# Arduino-Mega-2560-Adapter_2.net
KiCad netlist of a schematic drawn in EAGLE
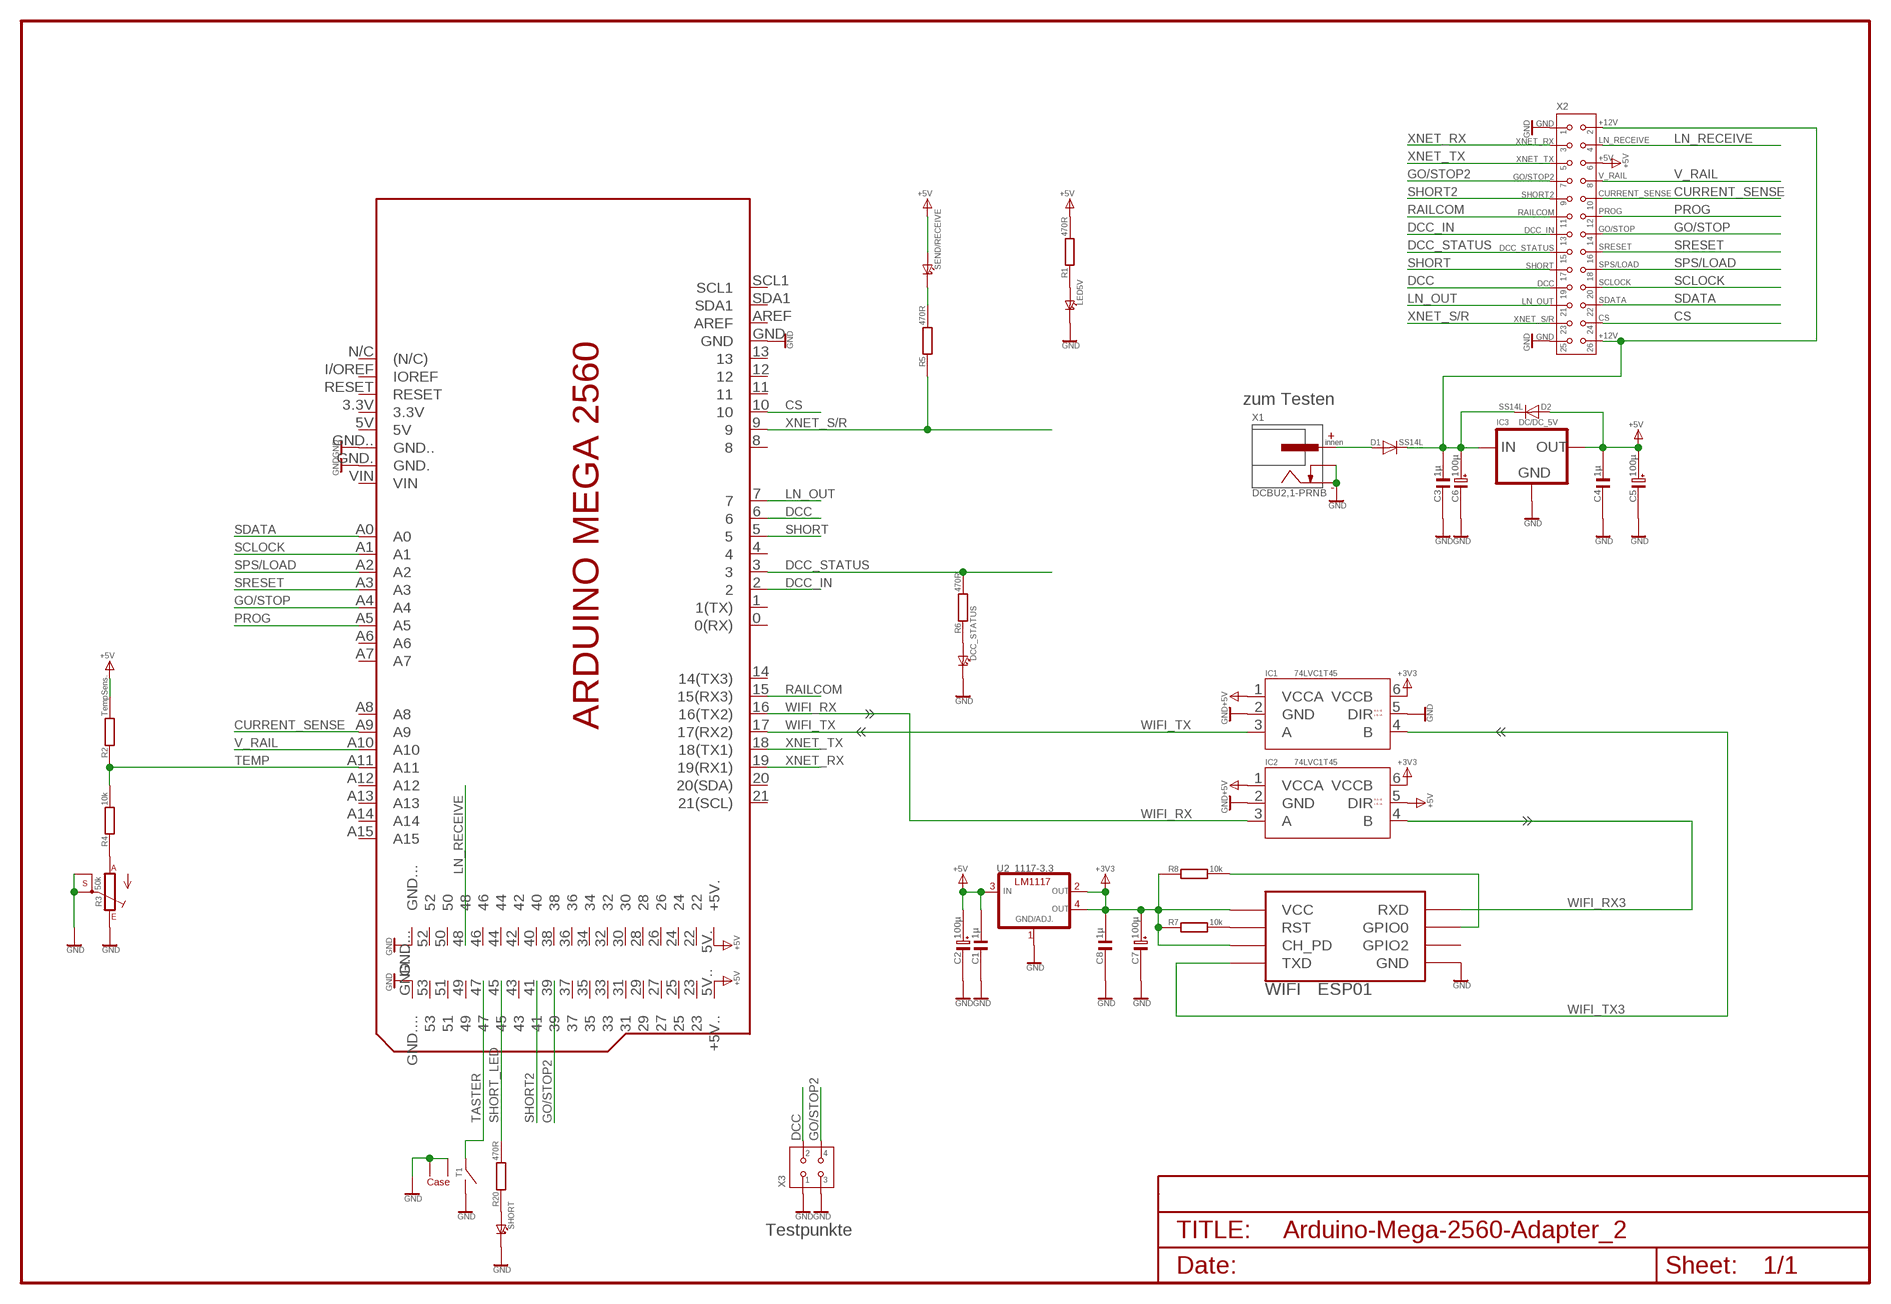
[diagram p0: schematic, sheet 1]

(export (version "E")
  (design (tool "Eeschema 10.0.6"))
  (components
    (comp (ref "C1")
      (value "1µ")
      (footprint "eagle-import:C0805")
      (libsource (lib "eagle-import") (part "C0805"))
    )
    (comp (ref "C2")
      (value "100µ")
      (footprint "eagle-import:RM2.5_DIA6")
      (libsource (lib "eagle-import") (part "ELKORM2.5_DIA6"))
    )
    (comp (ref "C3")
      (value "1µ")
      (footprint "eagle-import:C0805")
      (libsource (lib "eagle-import") (part "C0805"))
    )
    (comp (ref "C4")
      (value "1µ")
      (footprint "eagle-import:C0805")
      (libsource (lib "eagle-import") (part "C0805"))
    )
    (comp (ref "C5")
      (value "100µ")
      (footprint "eagle-import:RM2.5_DIA6")
      (libsource (lib "eagle-import") (part "ELKORM2.5_DIA6"))
    )
    (comp (ref "C6")
      (value "100µ")
      (footprint "eagle-import:RM2.5_DIA6")
      (libsource (lib "eagle-import") (part "ELKORM2.5_DIA6"))
    )
    (comp (ref "C7")
      (value "100µ")
      (footprint "eagle-import:RM2.5_DIA6")
      (libsource (lib "eagle-import") (part "ELKORM2.5_DIA6"))
    )
    (comp (ref "C8")
      (value "1µ")
      (footprint "eagle-import:C0805")
      (libsource (lib "eagle-import") (part "C0805"))
    )
    (comp (ref "D1")
      (value "SS14L")
      (footprint "eagle-import:SUB-SMA_")
      (libsource (lib "eagle-import") (part "DIODESUB-SMA_"))
    )
    (comp (ref "D2")
      (value "SS14L")
      (footprint "eagle-import:SUB-SMA_")
      (libsource (lib "eagle-import") (part "DIODESUB-SMA_"))
    )
    (comp (ref "DCC_STATUS")
      (value "LED3MM_")
      (footprint "eagle-import:LED3MM_")
      (libsource (lib "eagle-import") (part "LED3MM_"))
    )
    (comp (ref "IC1")
      (value "74LVC1T45")
      (footprint "eagle-import:SOT23-6_")
      (libsource (lib "eagle-import") (part "74LVC1T45SOT23-6"))
    )
    (comp (ref "IC2")
      (value "74LVC1T45")
      (footprint "eagle-import:SOT23-6_")
      (libsource (lib "eagle-import") (part "74LVC1T45SOT23-6"))
    )
    (comp (ref "IC3")
      (value "DC/DC_5V")
      (footprint "eagle-import:78XXS")
      (libsource (lib "eagle-import") (part "78XXLSTEHEND"))
    )
    (comp (ref "LED5V")
      (value "LED3MM_")
      (footprint "eagle-import:LED3MM_")
      (libsource (lib "eagle-import") (part "LED3MM_"))
    )
    (comp (ref "PCB1")
      (value "ARDUINO_MEGA2560")
      (footprint "eagle-import:ARDUINO_MEGA2560")
      (libsource (lib "eagle-import") (part "ARDUINO_MEGA2560"))
    )
    (comp (ref "R1")
      (value "470R")
      (footprint "eagle-import:R0805")
      (libsource (lib "eagle-import") (part "R0805"))
    )
    (comp (ref "R2")
      (value "TempSens.")
      (footprint "eagle-import:RM02,5")
      (libsource (lib "eagle-import") (part "RRM2,5"))
    )
    (comp (ref "R3")
      (value "50k")
      (footprint "eagle-import:S64YW")
      (libsource (lib "eagle-import") (part "TRIM_1234-S64YW"))
    )
    (comp (ref "R4")
      (value "10k")
      (footprint "eagle-import:R0603")
      (libsource (lib "eagle-import") (part "R0603"))
    )
    (comp (ref "R5")
      (value "470R")
      (footprint "eagle-import:R0805")
      (libsource (lib "eagle-import") (part "R0805"))
    )
    (comp (ref "R6")
      (value "470R")
      (footprint "eagle-import:R0805")
      (libsource (lib "eagle-import") (part "R0805"))
    )
    (comp (ref "R7")
      (value "10k")
      (footprint "eagle-import:R0603")
      (libsource (lib "eagle-import") (part "R0603"))
    )
    (comp (ref "R8")
      (value "10k")
      (footprint "eagle-import:R0603")
      (libsource (lib "eagle-import") (part "R0603"))
    )
    (comp (ref "R20")
      (value "470R")
      (footprint "eagle-import:R0805")
      (libsource (lib "eagle-import") (part "R0805"))
    )
    (comp (ref "SEND/RECEIVE")
      (value "LED3MM_")
      (footprint "eagle-import:LED3MM_")
      (libsource (lib "eagle-import") (part "LED3MM_"))
    )
    (comp (ref "SHORT")
      (value "LED3MM_")
      (footprint "eagle-import:LED3MM_")
      (libsource (lib "eagle-import") (part "LED3MM_"))
    )
    (comp (ref "T1")
      (value "TACT6060-90°")
      (footprint "eagle-import:TACT6060-90°_")
      (libsource (lib "eagle-import") (part "TACT6060-90°_"))
    )
    (comp (ref "U2")
      (value "1117-3,3")
      (footprint "eagle-import:SOT223__")
      (libsource (lib "eagle-import") (part "LM1117_"))
    )
    (comp (ref "WIFI")
      (value "ESP01")
      (footprint "eagle-import:ESP01")
      (libsource (lib "eagle-import") (part "ESP01"))
    )
    (comp (ref "X1")
      (value "DCBU2,1-PRNB")
      (footprint "eagle-import:DCBU2,1-PRNB")
      (libsource (lib "eagle-import") (part "DC-BUCHSE2DCBU2,1-PRNB"))
    )
    (comp (ref "X2")
      (value "2X13_WANNE_180°")
      (footprint "eagle-import:2X13_WANNE_180°")
      (libsource (lib "eagle-import") (part "2X13_WANNE_180°"))
    )
    (comp (ref "X3")
      (value "2X02_2.54MM")
      (footprint "eagle-import:2X02_2.54MM")
      (libsource (lib "eagle-import") (part "2X02_2.54MM"))
    )
  )
  (nets
    (net (code "1") (name "+3V3") (class "Default")
      (node (ref "C7") (pin "PLUS") (pinfunction "PLUS_PLUS") (pintype "bidirectional"))
      (node (ref "C8") (pin "2") (pinfunction "P$2_2") (pintype "bidirectional"))
      (node (ref "IC1") (pin "6") (pinfunction "VCCB_6") (pintype "bidirectional"))
      (node (ref "IC2") (pin "6") (pinfunction "VCCB_6") (pintype "bidirectional"))
      (node (ref "R7") (pin "P$1") (pinfunction "P$1_P$1") (pintype "bidirectional"))
      (node (ref "R8") (pin "P$1") (pinfunction "P$1_P$1") (pintype "bidirectional"))
      (node (ref "U2") (pin "2") (pinfunction "OUT_2") (pintype "passive"))
      (node (ref "U2") (pin "4") (pinfunction "OUT1_4") (pintype "passive"))
      (node (ref "WIFI") (pin "CH_PD") (pinfunction "CH_PD_CH_PD") (pintype "bidirectional"))
      (node (ref "WIFI") (pin "VCC") (pinfunction "VCC_VCC") (pintype "bidirectional"))
    )
    (net (code "2") (name "+5V") (class "Default")
      (node (ref "C1") (pin "2") (pinfunction "P$2_2") (pintype "bidirectional"))
      (node (ref "C2") (pin "PLUS") (pinfunction "PLUS_PLUS") (pintype "bidirectional"))
      (node (ref "C4") (pin "2") (pinfunction "P$2_2") (pintype "bidirectional"))
      (node (ref "C5") (pin "PLUS") (pinfunction "PLUS_PLUS") (pintype "bidirectional"))
      (node (ref "D2") (pin "A") (pinfunction "ANODE_A") (pintype "passive"))
      (node (ref "IC1") (pin "1") (pinfunction "VCCA_1") (pintype "bidirectional"))
      (node (ref "IC2") (pin "1") (pinfunction "VCCA_1") (pintype "bidirectional"))
      (node (ref "IC2") (pin "5") (pinfunction "DIR_5") (pintype "bidirectional"))
      (node (ref "IC3") (pin "OUT") (pinfunction "OUT_OUT") (pintype "passive"))
      (node (ref "PCB1") (pin "5V.") (pinfunction "+5V._5V.") (pintype "bidirectional"))
      (node (ref "PCB1") (pin "5V..") (pinfunction "+5V.._5V..") (pintype "bidirectional"))
      (node (ref "R1") (pin "P$2") (pinfunction "P$2_P$2") (pintype "bidirectional"))
      (node (ref "R2") (pin "P$2") (pinfunction "P$2_P$2") (pintype "bidirectional"))
      (node (ref "SEND/RECEIVE") (pin "A") (pinfunction "ANODE_A") (pintype "bidirectional"))
      (node (ref "U2") (pin "3") (pinfunction "IN_3") (pintype "input"))
      (node (ref "X2") (pin "P$6") (pinfunction "P$6_P$6") (pintype "bidirectional"))
    )
    (net (code "3") (name "/CS") (class "Default")
      (node (ref "PCB1") (pin "10") (pinfunction "10_10") (pintype "bidirectional"))
      (node (ref "X2") (pin "P$24") (pinfunction "P$24_P$24") (pintype "bidirectional"))
    )
    (net (code "4") (name "/CURRENT_SENSE") (class "Default")
      (node (ref "PCB1") (pin "A9") (pinfunction "A9_A9") (pintype "bidirectional"))
      (node (ref "X2") (pin "P$10") (pinfunction "P$10_P$10") (pintype "bidirectional"))
    )
    (net (code "5") (name "/DCC") (class "Default")
      (node (ref "PCB1") (pin "6") (pinfunction "6_6") (pintype "bidirectional"))
      (node (ref "X2") (pin "P$19") (pinfunction "P$19_P$19") (pintype "bidirectional"))
      (node (ref "X3") (pin "P$2") (pinfunction "P$2_P$2") (pintype "bidirectional"))
    )
    (net (code "6") (name "/DCC_IN") (class "Default")
      (node (ref "PCB1") (pin "2") (pinfunction "2_2") (pintype "bidirectional"))
      (node (ref "X2") (pin "P$13") (pinfunction "P$13_P$13") (pintype "bidirectional"))
    )
    (net (code "7") (name "/DCC_STATUS") (class "Default")
      (node (ref "PCB1") (pin "3") (pinfunction "3_3") (pintype "bidirectional"))
      (node (ref "R6") (pin "P$2") (pinfunction "P$2_P$2") (pintype "bidirectional"))
      (node (ref "X2") (pin "P$15") (pinfunction "P$15_P$15") (pintype "bidirectional"))
    )
    (net (code "8") (name "/GO{slash}STOP") (class "Default")
      (node (ref "PCB1") (pin "A4") (pinfunction "A4_A4") (pintype "bidirectional"))
      (node (ref "X2") (pin "P$14") (pinfunction "P$14_P$14") (pintype "bidirectional"))
    )
    (net (code "9") (name "/GO{slash}STOP2") (class "Default")
      (node (ref "PCB1") (pin "39") (pinfunction "39_39") (pintype "bidirectional"))
      (node (ref "X2") (pin "P$7") (pinfunction "P$7_P$7") (pintype "bidirectional"))
      (node (ref "X3") (pin "P$4") (pinfunction "P$4_P$4") (pintype "bidirectional"))
    )
    (net (code "10") (name "/LN_OUT") (class "Default")
      (node (ref "PCB1") (pin "7") (pinfunction "7_7") (pintype "bidirectional"))
      (node (ref "X2") (pin "P$21") (pinfunction "P$21_P$21") (pintype "bidirectional"))
    )
    (net (code "11") (name "/LN_RECEIVE") (class "Default")
      (node (ref "PCB1") (pin "48") (pinfunction "48_48") (pintype "bidirectional"))
      (node (ref "X2") (pin "P$4") (pinfunction "P$4_P$4") (pintype "bidirectional"))
    )
    (net (code "12") (name "/PROG") (class "Default")
      (node (ref "PCB1") (pin "A5") (pinfunction "A5_A5") (pintype "bidirectional"))
      (node (ref "X2") (pin "P$12") (pinfunction "P$12_P$12") (pintype "bidirectional"))
    )
    (net (code "13") (name "/RAILCOM") (class "Default")
      (node (ref "PCB1") (pin "15") (pinfunction "15(RX3)_15") (pintype "bidirectional"))
      (node (ref "X2") (pin "P$11") (pinfunction "P$11_P$11") (pintype "bidirectional"))
    )
    (net (code "14") (name "/SCLOCK") (class "Default")
      (node (ref "PCB1") (pin "A1") (pinfunction "A1_A1") (pintype "bidirectional"))
      (node (ref "X2") (pin "P$20") (pinfunction "P$20_P$20") (pintype "bidirectional"))
    )
    (net (code "15") (name "/SDATA") (class "Default")
      (node (ref "PCB1") (pin "A0") (pinfunction "A0_A0") (pintype "bidirectional"))
      (node (ref "X2") (pin "P$22") (pinfunction "P$22_P$22") (pintype "bidirectional"))
    )
    (net (code "16") (name "/SHORT") (class "Default")
      (node (ref "PCB1") (pin "5") (pinfunction "5_5") (pintype "bidirectional"))
      (node (ref "X2") (pin "P$17") (pinfunction "P$17_P$17") (pintype "bidirectional"))
    )
    (net (code "17") (name "/SHORT2") (class "Default")
      (node (ref "PCB1") (pin "41") (pinfunction "41_41") (pintype "bidirectional"))
      (node (ref "X2") (pin "P$9") (pinfunction "P$9_P$9") (pintype "bidirectional"))
    )
    (net (code "18") (name "/SHORT_LED") (class "Default")
      (node (ref "PCB1") (pin "45") (pinfunction "45_45") (pintype "bidirectional"))
      (node (ref "R20") (pin "P$2") (pinfunction "P$2_P$2") (pintype "bidirectional"))
    )
    (net (code "19") (name "/SPS{slash}LOAD") (class "Default")
      (node (ref "PCB1") (pin "A2") (pinfunction "A2_A2") (pintype "bidirectional"))
      (node (ref "X2") (pin "P$18") (pinfunction "P$18_P$18") (pintype "bidirectional"))
    )
    (net (code "20") (name "/SRESET") (class "Default")
      (node (ref "PCB1") (pin "A3") (pinfunction "A3_A3") (pintype "bidirectional"))
      (node (ref "X2") (pin "P$16") (pinfunction "P$16_P$16") (pintype "bidirectional"))
    )
    (net (code "21") (name "/TASTER") (class "Default")
      (node (ref "PCB1") (pin "47") (pinfunction "47_47") (pintype "bidirectional"))
      (node (ref "T1") (pin "2") (pinfunction "P$2_2") (pintype "bidirectional"))
    )
    (net (code "22") (name "/TEMP") (class "Default")
      (node (ref "PCB1") (pin "A11") (pinfunction "A11_A11") (pintype "bidirectional"))
      (node (ref "R2") (pin "P$1") (pinfunction "P$1_P$1") (pintype "bidirectional"))
      (node (ref "R4") (pin "P$2") (pinfunction "P$2_P$2") (pintype "bidirectional"))
    )
    (net (code "23") (name "/V_RAIL") (class "Default")
      (node (ref "PCB1") (pin "A10") (pinfunction "A10_A10") (pintype "bidirectional"))
      (node (ref "X2") (pin "P$8") (pinfunction "P$8_P$8") (pintype "bidirectional"))
    )
    (net (code "24") (name "/WIFI_RX") (class "Default")
      (node (ref "IC2") (pin "3") (pinfunction "A_3") (pintype "bidirectional"))
      (node (ref "PCB1") (pin "16") (pinfunction "16(TX2)_16") (pintype "bidirectional"))
    )
    (net (code "25") (name "/WIFI_RX3") (class "Default")
      (node (ref "IC2") (pin "4") (pinfunction "B_4") (pintype "bidirectional"))
      (node (ref "WIFI") (pin "RX") (pinfunction "RXD_RX") (pintype "bidirectional"))
    )
    (net (code "26") (name "/WIFI_TX") (class "Default")
      (node (ref "IC1") (pin "3") (pinfunction "A_3") (pintype "bidirectional"))
      (node (ref "PCB1") (pin "17") (pinfunction "17(RX2)_17") (pintype "bidirectional"))
    )
    (net (code "27") (name "/WIFI_TX3") (class "Default")
      (node (ref "IC1") (pin "4") (pinfunction "B_4") (pintype "bidirectional"))
      (node (ref "WIFI") (pin "TX") (pinfunction "TXD_TX") (pintype "bidirectional"))
    )
    (net (code "28") (name "/XNET_RX") (class "Default")
      (node (ref "PCB1") (pin "19") (pinfunction "19(RX1)_19") (pintype "bidirectional"))
      (node (ref "X2") (pin "P$3") (pinfunction "P$3_P$3") (pintype "bidirectional"))
    )
    (net (code "29") (name "/XNET_S{slash}R") (class "Default")
      (node (ref "PCB1") (pin "9") (pinfunction "9_9") (pintype "bidirectional"))
      (node (ref "R5") (pin "P$1") (pinfunction "P$1_P$1") (pintype "bidirectional"))
      (node (ref "X2") (pin "P$23") (pinfunction "P$23_P$23") (pintype "bidirectional"))
    )
    (net (code "30") (name "/XNET_TX") (class "Default")
      (node (ref "PCB1") (pin "18") (pinfunction "18(TX1)_18") (pintype "bidirectional"))
      (node (ref "X2") (pin "P$5") (pinfunction "P$5_P$5") (pintype "bidirectional"))
    )
    (net (code "31") (name "GND") (class "Default")
      (node (ref "C1") (pin "1") (pinfunction "P$1_1") (pintype "bidirectional"))
      (node (ref "C2") (pin "MINUS") (pinfunction "MINUS_MINUS") (pintype "bidirectional"))
      (node (ref "C3") (pin "1") (pinfunction "P$1_1") (pintype "bidirectional"))
      (node (ref "C4") (pin "1") (pinfunction "P$1_1") (pintype "bidirectional"))
      (node (ref "C5") (pin "MINUS") (pinfunction "MINUS_MINUS") (pintype "bidirectional"))
      (node (ref "C6") (pin "MINUS") (pinfunction "MINUS_MINUS") (pintype "bidirectional"))
      (node (ref "C7") (pin "MINUS") (pinfunction "MINUS_MINUS") (pintype "bidirectional"))
      (node (ref "C8") (pin "1") (pinfunction "P$1_1") (pintype "bidirectional"))
      (node (ref "DCC_STATUS") (pin "K") (pinfunction "KATHODE_K") (pintype "bidirectional"))
      (node (ref "IC1") (pin "2") (pinfunction "GND_2") (pintype "bidirectional"))
      (node (ref "IC1") (pin "5") (pinfunction "DIR_5") (pintype "bidirectional"))
      (node (ref "IC2") (pin "2") (pinfunction "GND_2") (pintype "bidirectional"))
      (node (ref "IC3") (pin "GND") (pinfunction "GND_GND") (pintype "input"))
      (node (ref "LED5V") (pin "K") (pinfunction "KATHODE_K") (pintype "bidirectional"))
      (node (ref "PCB1") (pin "GND") (pinfunction "GND_GND") (pintype "bidirectional"))
      (node (ref "PCB1") (pin "GND.") (pinfunction "GND._GND.") (pintype "bidirectional"))
      (node (ref "PCB1") (pin "GND..") (pinfunction "GND.._GND..") (pintype "bidirectional"))
      (node (ref "PCB1") (pin "GND...") (pinfunction "GND..._GND...") (pintype "bidirectional"))
      (node (ref "PCB1") (pin "GND....") (pinfunction "GND...._GND....") (pintype "bidirectional"))
      (node (ref "R3") (pin "E") (pinfunction "E_E") (pintype "passive"))
      (node (ref "R3") (pin "S") (pinfunction "S_S") (pintype "passive"))
      (node (ref "R3") (pin "S@1") (pinfunction "S_S@1") (pintype "passive"))
      (node (ref "SHORT") (pin "K") (pinfunction "KATHODE_K") (pintype "bidirectional"))
      (node (ref "T1") (pin "1") (pinfunction "P$1_1") (pintype "bidirectional"))
      (node (ref "T1") (pin "3") (pinfunction "CASE_3") (pintype "bidirectional"))
      (node (ref "T1") (pin "4") (pinfunction "CASE_4") (pintype "bidirectional"))
      (node (ref "U2") (pin "1") (pinfunction "GND_1") (pintype "input"))
      (node (ref "WIFI") (pin "GND") (pinfunction "GND_GND") (pintype "bidirectional"))
      (node (ref "X1") (pin "AUßEN") (pinfunction "AUßEN_AUßEN") (pintype "passive"))
      (node (ref "X1") (pin "ÖFFNER") (pinfunction "ÖFFNER_ÖFFNER") (pintype "passive"))
      (node (ref "X2") (pin "P$1") (pinfunction "P$1_P$1") (pintype "bidirectional"))
      (node (ref "X2") (pin "P$25") (pinfunction "P$25_P$25") (pintype "bidirectional"))
      (node (ref "X3") (pin "P$1") (pinfunction "P$1_P$1") (pintype "bidirectional"))
      (node (ref "X3") (pin "P$3") (pinfunction "P$3_P$3") (pintype "bidirectional"))
    )
    (net (code "32") (name "Net-(C3-P$2)") (class "Default")
      (node (ref "C3") (pin "2") (pinfunction "P$2_2") (pintype "bidirectional"))
      (node (ref "C6") (pin "PLUS") (pinfunction "PLUS_PLUS") (pintype "bidirectional"))
      (node (ref "D1") (pin "K") (pinfunction "KATHODE_K") (pintype "passive"))
      (node (ref "D2") (pin "K") (pinfunction "KATHODE_K") (pintype "passive"))
      (node (ref "IC3") (pin "IN") (pinfunction "IN_IN") (pintype "input"))
      (node (ref "X2") (pin "P$2") (pinfunction "P$2_P$2") (pintype "bidirectional"))
      (node (ref "X2") (pin "P$26") (pinfunction "P$26_P$26") (pintype "bidirectional"))
    )
    (net (code "33") (name "Net-(D1-ANODE)") (class "Default")
      (node (ref "D1") (pin "A") (pinfunction "ANODE_A") (pintype "passive"))
      (node (ref "X1") (pin "INNEN") (pinfunction "INNEN_INNEN") (pintype "passive"))
    )
    (net (code "34") (name "Net-(DCC_STATUS-ANODE)") (class "Default")
      (node (ref "DCC_STATUS") (pin "A") (pinfunction "ANODE_A") (pintype "bidirectional"))
      (node (ref "R6") (pin "P$1") (pinfunction "P$1_P$1") (pintype "bidirectional"))
    )
    (net (code "35") (name "Net-(LED5V-ANODE)") (class "Default")
      (node (ref "LED5V") (pin "A") (pinfunction "ANODE_A") (pintype "bidirectional"))
      (node (ref "R1") (pin "P$1") (pinfunction "P$1_P$1") (pintype "bidirectional"))
    )
    (net (code "36") (name "Net-(R3-PadA)") (class "Default")
      (node (ref "R3") (pin "A") (pinfunction "A_A") (pintype "passive"))
      (node (ref "R4") (pin "P$1") (pinfunction "P$1_P$1") (pintype "bidirectional"))
    )
    (net (code "37") (name "Net-(R7-PadP$2)") (class "Default")
      (node (ref "R7") (pin "P$2") (pinfunction "P$2_P$2") (pintype "bidirectional"))
      (node (ref "WIFI") (pin "RST") (pinfunction "RST_RST") (pintype "bidirectional"))
    )
    (net (code "38") (name "Net-(R8-PadP$2)") (class "Default")
      (node (ref "R8") (pin "P$2") (pinfunction "P$2_P$2") (pintype "bidirectional"))
      (node (ref "WIFI") (pin "GPIO0") (pinfunction "GPIO0_GPIO0") (pintype "bidirectional"))
    )
    (net (code "39") (name "Net-(SEND/RECEIVE-KATHODE)") (class "Default")
      (node (ref "R5") (pin "P$2") (pinfunction "P$2_P$2") (pintype "bidirectional"))
      (node (ref "SEND/RECEIVE") (pin "K") (pinfunction "KATHODE_K") (pintype "bidirectional"))
    )
    (net (code "40") (name "Net-(SHORT-ANODE)") (class "Default")
      (node (ref "R20") (pin "P$1") (pinfunction "P$1_P$1") (pintype "bidirectional"))
      (node (ref "SHORT") (pin "A") (pinfunction "ANODE_A") (pintype "bidirectional"))
    )
    (net (code "41") (name "unconnected-(PCB1-(N{slash}C)-PadN{slash}C)") (class "Default")
      (node (ref "PCB1") (pin "N/C") (pinfunction "(N/C)_N/C") (pintype "bidirectional"))
    )
    (net (code "42") (name "unconnected-(PCB1-0(RX)-Pad0)") (class "Default")
      (node (ref "PCB1") (pin "0") (pinfunction "0(RX)_0") (pintype "bidirectional"))
    )
    (net (code "43") (name "unconnected-(PCB1-1(TX)-Pad1)") (class "Default")
      (node (ref "PCB1") (pin "1") (pinfunction "1(TX)_1") (pintype "bidirectional"))
    )
    (net (code "44") (name "unconnected-(PCB1-14(TX3)-Pad14)") (class "Default")
      (node (ref "PCB1") (pin "14") (pinfunction "14(TX3)_14") (pintype "bidirectional"))
    )
    (net (code "45") (name "unconnected-(PCB1-20(SDA)-Pad20)") (class "Default")
      (node (ref "PCB1") (pin "20") (pinfunction "20(SDA)_20") (pintype "bidirectional"))
    )
    (net (code "46") (name "unconnected-(PCB1-21(SCL)-Pad21)") (class "Default")
      (node (ref "PCB1") (pin "21") (pinfunction "21(SCL)_21") (pintype "bidirectional"))
    )
    (net (code "47") (name "unconnected-(PCB1-IOREF-PadI{slash}OREF)") (class "Default")
      (node (ref "PCB1") (pin "I/OREF") (pinfunction "IOREF_I/OREF") (pintype "bidirectional"))
    )
    (net (code "48") (name "unconnected-(PCB1-Pad3.3V)") (class "Default")
      (node (ref "PCB1") (pin "3.3V") (pinfunction "3.3V_3.3V") (pintype "bidirectional"))
    )
    (net (code "49") (name "unconnected-(PCB1-Pad4)") (class "Default")
      (node (ref "PCB1") (pin "4") (pinfunction "4_4") (pintype "bidirectional"))
    )
    (net (code "50") (name "unconnected-(PCB1-Pad5V)") (class "Default")
      (node (ref "PCB1") (pin "5V") (pinfunction "5V_5V") (pintype "bidirectional"))
    )
    (net (code "51") (name "unconnected-(PCB1-Pad8)") (class "Default")
      (node (ref "PCB1") (pin "8") (pinfunction "8_8") (pintype "bidirectional"))
    )
    (net (code "52") (name "unconnected-(PCB1-Pad11)") (class "Default")
      (node (ref "PCB1") (pin "11") (pinfunction "11_11") (pintype "bidirectional"))
    )
    (net (code "53") (name "unconnected-(PCB1-Pad12)") (class "Default")
      (node (ref "PCB1") (pin "12") (pinfunction "12_12") (pintype "bidirectional"))
    )
    (net (code "54") (name "unconnected-(PCB1-Pad13)") (class "Default")
      (node (ref "PCB1") (pin "13") (pinfunction "13_13") (pintype "bidirectional"))
    )
    (net (code "55") (name "unconnected-(PCB1-Pad22)") (class "Default")
      (node (ref "PCB1") (pin "22") (pinfunction "22_22") (pintype "bidirectional"))
    )
    (net (code "56") (name "unconnected-(PCB1-Pad23)") (class "Default")
      (node (ref "PCB1") (pin "23") (pinfunction "23_23") (pintype "bidirectional"))
    )
    (net (code "57") (name "unconnected-(PCB1-Pad24)") (class "Default")
      (node (ref "PCB1") (pin "24") (pinfunction "24_24") (pintype "bidirectional"))
    )
    (net (code "58") (name "unconnected-(PCB1-Pad25)") (class "Default")
      (node (ref "PCB1") (pin "25") (pinfunction "25_25") (pintype "bidirectional"))
    )
    (net (code "59") (name "unconnected-(PCB1-Pad26)") (class "Default")
      (node (ref "PCB1") (pin "26") (pinfunction "26_26") (pintype "bidirectional"))
    )
    (net (code "60") (name "unconnected-(PCB1-Pad27)") (class "Default")
      (node (ref "PCB1") (pin "27") (pinfunction "27_27") (pintype "bidirectional"))
    )
    (net (code "61") (name "unconnected-(PCB1-Pad28)") (class "Default")
      (node (ref "PCB1") (pin "28") (pinfunction "28_28") (pintype "bidirectional"))
    )
    (net (code "62") (name "unconnected-(PCB1-Pad29)") (class "Default")
      (node (ref "PCB1") (pin "29") (pinfunction "29_29") (pintype "bidirectional"))
    )
    (net (code "63") (name "unconnected-(PCB1-Pad30)") (class "Default")
      (node (ref "PCB1") (pin "30") (pinfunction "30_30") (pintype "bidirectional"))
    )
    (net (code "64") (name "unconnected-(PCB1-Pad31)") (class "Default")
      (node (ref "PCB1") (pin "31") (pinfunction "31_31") (pintype "bidirectional"))
    )
    (net (code "65") (name "unconnected-(PCB1-Pad32)") (class "Default")
      (node (ref "PCB1") (pin "32") (pinfunction "32_32") (pintype "bidirectional"))
    )
    (net (code "66") (name "unconnected-(PCB1-Pad33)") (class "Default")
      (node (ref "PCB1") (pin "33") (pinfunction "33_33") (pintype "bidirectional"))
    )
    (net (code "67") (name "unconnected-(PCB1-Pad34)") (class "Default")
      (node (ref "PCB1") (pin "34") (pinfunction "34_34") (pintype "bidirectional"))
    )
    (net (code "68") (name "unconnected-(PCB1-Pad35)") (class "Default")
      (node (ref "PCB1") (pin "35") (pinfunction "35_35") (pintype "bidirectional"))
    )
    (net (code "69") (name "unconnected-(PCB1-Pad36)") (class "Default")
      (node (ref "PCB1") (pin "36") (pinfunction "36_36") (pintype "bidirectional"))
    )
    (net (code "70") (name "unconnected-(PCB1-Pad37)") (class "Default")
      (node (ref "PCB1") (pin "37") (pinfunction "37_37") (pintype "bidirectional"))
    )
    (net (code "71") (name "unconnected-(PCB1-Pad38)") (class "Default")
      (node (ref "PCB1") (pin "38") (pinfunction "38_38") (pintype "bidirectional"))
    )
    (net (code "72") (name "unconnected-(PCB1-Pad40)") (class "Default")
      (node (ref "PCB1") (pin "40") (pinfunction "40_40") (pintype "bidirectional"))
    )
    (net (code "73") (name "unconnected-(PCB1-Pad42)") (class "Default")
      (node (ref "PCB1") (pin "42") (pinfunction "42_42") (pintype "bidirectional"))
    )
    (net (code "74") (name "unconnected-(PCB1-Pad43)") (class "Default")
      (node (ref "PCB1") (pin "43") (pinfunction "43_43") (pintype "bidirectional"))
    )
    (net (code "75") (name "unconnected-(PCB1-Pad44)") (class "Default")
      (node (ref "PCB1") (pin "44") (pinfunction "44_44") (pintype "bidirectional"))
    )
    (net (code "76") (name "unconnected-(PCB1-Pad46)") (class "Default")
      (node (ref "PCB1") (pin "46") (pinfunction "46_46") (pintype "bidirectional"))
    )
    (net (code "77") (name "unconnected-(PCB1-Pad49)") (class "Default")
      (node (ref "PCB1") (pin "49") (pinfunction "49_49") (pintype "bidirectional"))
    )
    (net (code "78") (name "unconnected-(PCB1-Pad50)") (class "Default")
      (node (ref "PCB1") (pin "50") (pinfunction "50_50") (pintype "bidirectional"))
    )
    (net (code "79") (name "unconnected-(PCB1-Pad51)") (class "Default")
      (node (ref "PCB1") (pin "51") (pinfunction "51_51") (pintype "bidirectional"))
    )
    (net (code "80") (name "unconnected-(PCB1-Pad52)") (class "Default")
      (node (ref "PCB1") (pin "52") (pinfunction "52_52") (pintype "bidirectional"))
    )
    (net (code "81") (name "unconnected-(PCB1-Pad53)") (class "Default")
      (node (ref "PCB1") (pin "53") (pinfunction "53_53") (pintype "bidirectional"))
    )
    (net (code "82") (name "unconnected-(PCB1-PadA6)") (class "Default")
      (node (ref "PCB1") (pin "A6") (pinfunction "A6_A6") (pintype "bidirectional"))
    )
    (net (code "83") (name "unconnected-(PCB1-PadA7)") (class "Default")
      (node (ref "PCB1") (pin "A7") (pinfunction "A7_A7") (pintype "bidirectional"))
    )
    (net (code "84") (name "unconnected-(PCB1-PadA8)") (class "Default")
      (node (ref "PCB1") (pin "A8") (pinfunction "A8_A8") (pintype "bidirectional"))
    )
    (net (code "85") (name "unconnected-(PCB1-PadA12)") (class "Default")
      (node (ref "PCB1") (pin "A12") (pinfunction "A12_A12") (pintype "bidirectional"))
    )
    (net (code "86") (name "unconnected-(PCB1-PadA13)") (class "Default")
      (node (ref "PCB1") (pin "A13") (pinfunction "A13_A13") (pintype "bidirectional"))
    )
    (net (code "87") (name "unconnected-(PCB1-PadA14)") (class "Default")
      (node (ref "PCB1") (pin "A14") (pinfunction "A14_A14") (pintype "bidirectional"))
    )
    (net (code "88") (name "unconnected-(PCB1-PadA15)") (class "Default")
      (node (ref "PCB1") (pin "A15") (pinfunction "A15_A15") (pintype "bidirectional"))
    )
    (net (code "89") (name "unconnected-(PCB1-PadAREF)") (class "Default")
      (node (ref "PCB1") (pin "AREF") (pinfunction "AREF_AREF") (pintype "bidirectional"))
    )
    (net (code "90") (name "unconnected-(PCB1-PadRESET)") (class "Default")
      (node (ref "PCB1") (pin "RESET") (pinfunction "RESET_RESET") (pintype "bidirectional"))
    )
    (net (code "91") (name "unconnected-(PCB1-PadSCL1)") (class "Default")
      (node (ref "PCB1") (pin "SCL1") (pinfunction "SCL1_SCL1") (pintype "bidirectional"))
    )
    (net (code "92") (name "unconnected-(PCB1-PadSDA1)") (class "Default")
      (node (ref "PCB1") (pin "SDA1") (pinfunction "SDA1_SDA1") (pintype "bidirectional"))
    )
    (net (code "93") (name "unconnected-(PCB1-PadVIN)") (class "Default")
      (node (ref "PCB1") (pin "VIN") (pinfunction "VIN_VIN") (pintype "bidirectional"))
    )
    (net (code "94") (name "unconnected-(WIFI-PadGPIO2)") (class "Default")
      (node (ref "WIFI") (pin "GPIO2") (pinfunction "GPIO2_GPIO2") (pintype "bidirectional"))
    )
  )
)
